# TTL640x480-DIODE.net
KiCad netlist of a schematic drawn in EAGLE
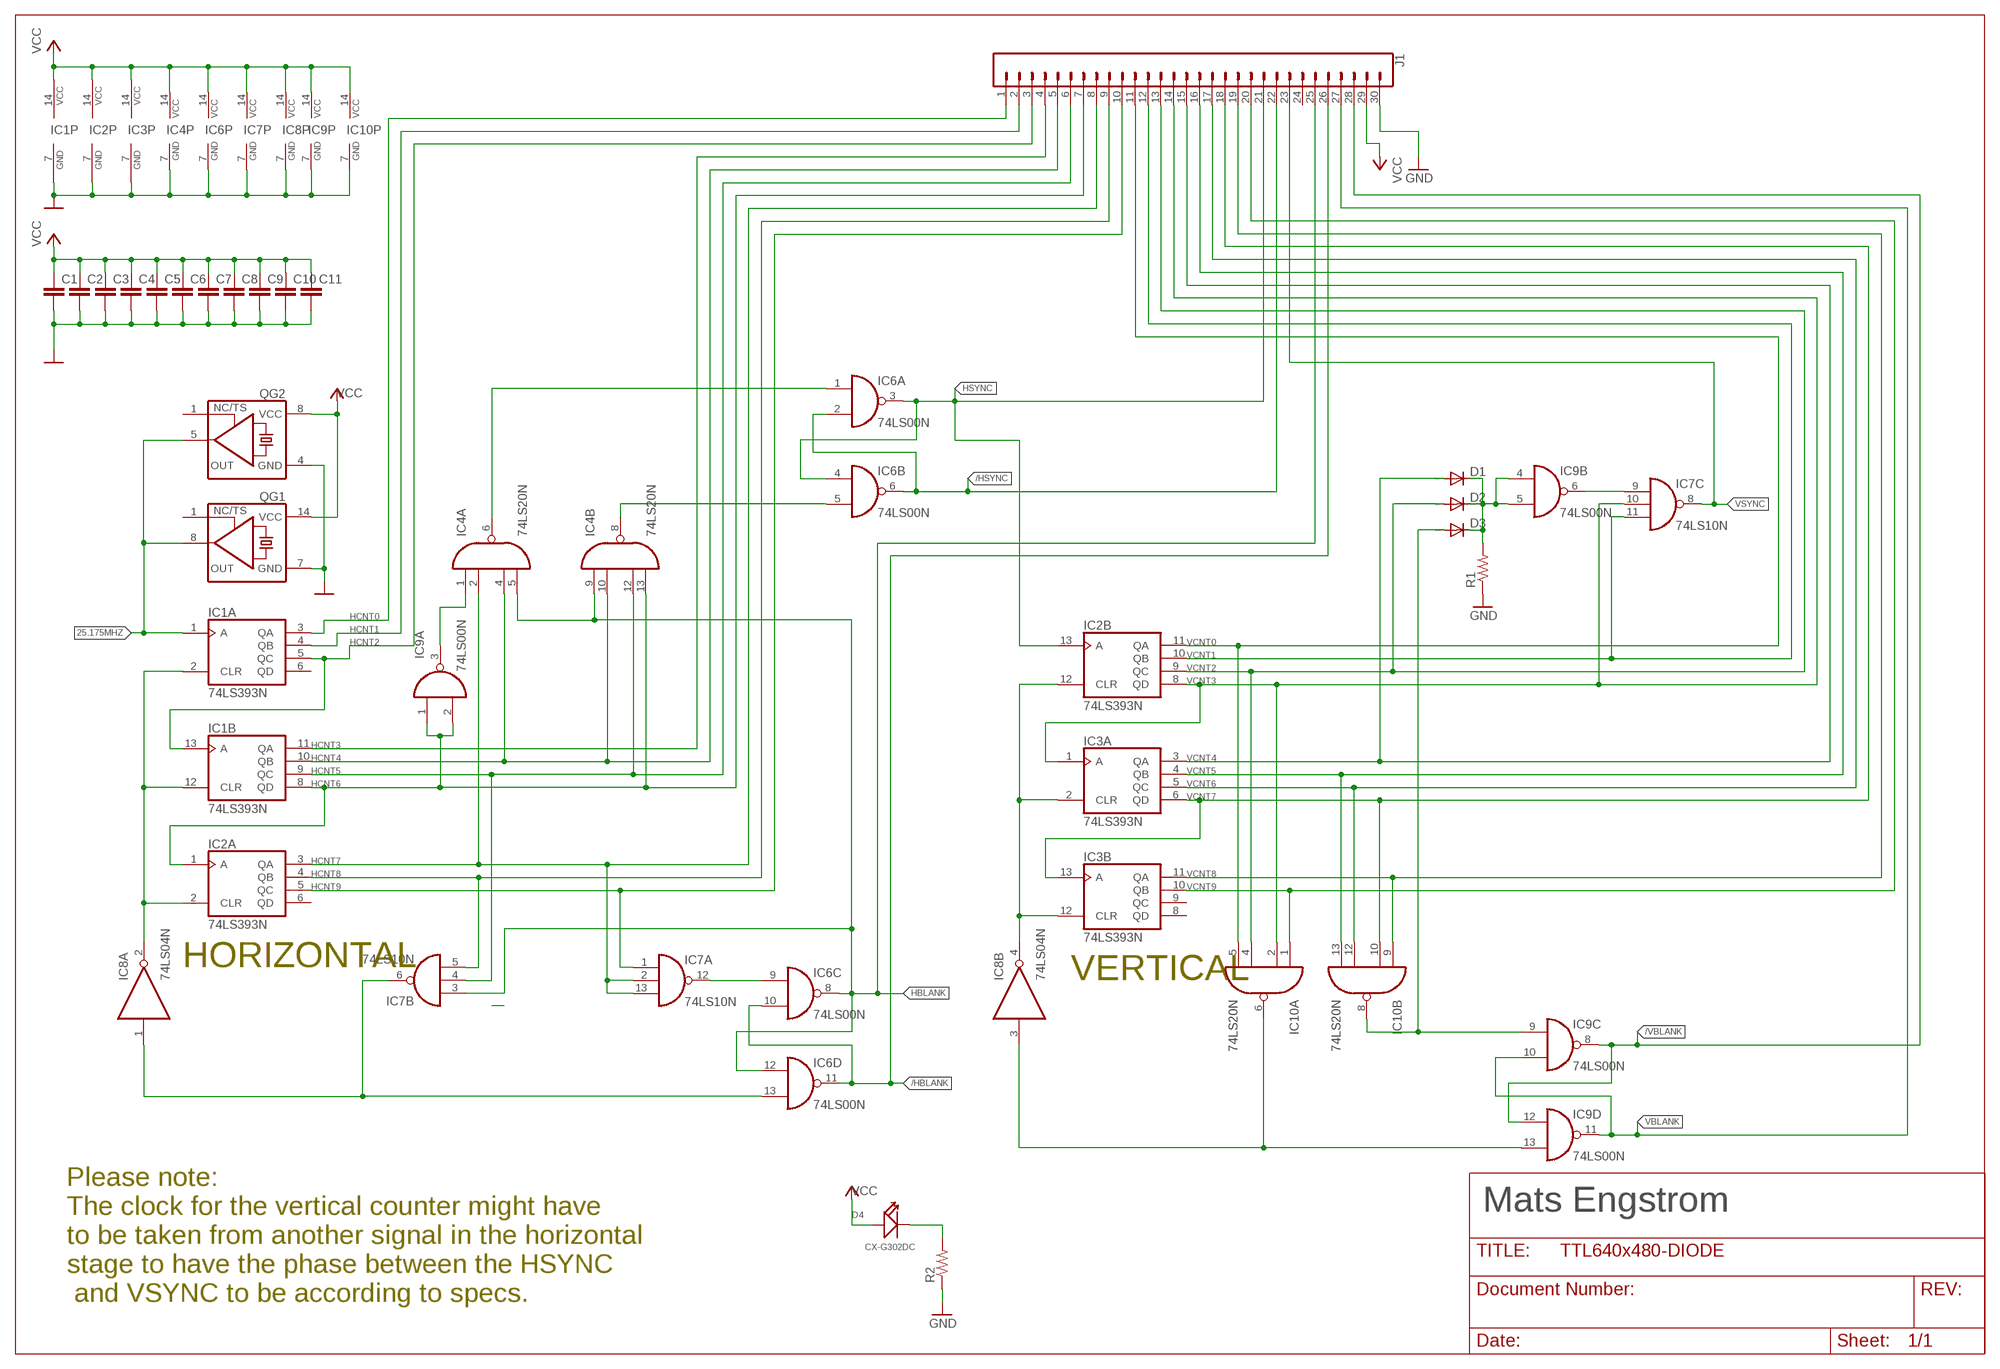
[diagram p0: schematic, sheet 1]

(export (version "E")
  (design (tool "Eeschema 10.0.6"))
  (components
    (comp (ref "C1")
      (value "C-EU050-024X044")
      (footprint "eagle-import:C050-024X044")
      (libsource (lib "eagle-import") (part "C-EU050-024X044"))
    )
    (comp (ref "C2")
      (value "C-EU050-024X044")
      (footprint "eagle-import:C050-024X044")
      (libsource (lib "eagle-import") (part "C-EU050-024X044"))
    )
    (comp (ref "C3")
      (value "C-EU050-024X044")
      (footprint "eagle-import:C050-024X044")
      (libsource (lib "eagle-import") (part "C-EU050-024X044"))
    )
    (comp (ref "C4")
      (value "C-EU050-024X044")
      (footprint "eagle-import:C050-024X044")
      (libsource (lib "eagle-import") (part "C-EU050-024X044"))
    )
    (comp (ref "C5")
      (value "C-EU050-024X044")
      (footprint "eagle-import:C050-024X044")
      (libsource (lib "eagle-import") (part "C-EU050-024X044"))
    )
    (comp (ref "C6")
      (value "C-EU050-024X044")
      (footprint "eagle-import:C050-024X044")
      (libsource (lib "eagle-import") (part "C-EU050-024X044"))
    )
    (comp (ref "C7")
      (value "C-EU050-024X044")
      (footprint "eagle-import:C050-024X044")
      (libsource (lib "eagle-import") (part "C-EU050-024X044"))
    )
    (comp (ref "C8")
      (value "C-EU050-024X044")
      (footprint "eagle-import:C050-024X044")
      (libsource (lib "eagle-import") (part "C-EU050-024X044"))
    )
    (comp (ref "C9")
      (value "C-EU050-024X044")
      (footprint "eagle-import:C050-024X044")
      (libsource (lib "eagle-import") (part "C-EU050-024X044"))
    )
    (comp (ref "C10")
      (value "C-EU050-024X044")
      (footprint "eagle-import:C050-024X044")
      (libsource (lib "eagle-import") (part "C-EU050-024X044"))
    )
    (comp (ref "C11")
      (value "C-EU050-024X044")
      (footprint "eagle-import:C050-024X044")
      (libsource (lib "eagle-import") (part "C-EU050-024X044"))
    )
    (comp (ref "D1")
      (value "1N4148DO35-10")
      (footprint "eagle-import:DO35-10")
      (libsource (lib "eagle-import") (part "1N4148DO35-10"))
    )
    (comp (ref "D2")
      (value "1N4148DO35-10")
      (footprint "eagle-import:DO35-10")
      (libsource (lib "eagle-import") (part "1N4148DO35-10"))
    )
    (comp (ref "D3")
      (value "1N4148DO35-10")
      (footprint "eagle-import:DO35-10")
      (libsource (lib "eagle-import") (part "1N4148DO35-10"))
    )
    (comp (ref "D4")
      (value "CX-G302DC")
      (footprint "eagle-import:LED2-2.54-D3.0MM")
      (libsource (lib "eagle-import") (part "DIP-LED-GREEN-GREEN(2P-D3MM)"))
    )
    (comp (ref "IC1")
      (value "74LS393N")
      (footprint "eagle-import:DIL14")
      (libsource (lib "eagle-import") (part "74393NLS"))
    )
    (comp (ref "IC2")
      (value "74LS393N")
      (footprint "eagle-import:DIL14")
      (libsource (lib "eagle-import") (part "74393NLS"))
    )
    (comp (ref "IC3")
      (value "74LS393N")
      (footprint "eagle-import:DIL14")
      (libsource (lib "eagle-import") (part "74393NLS"))
    )
    (comp (ref "IC4")
      (value "74LS20N")
      (footprint "eagle-import:DIL14")
      (libsource (lib "eagle-import") (part "7420NLS"))
    )
    (comp (ref "IC6")
      (value "74LS00N")
      (footprint "eagle-import:DIL14")
      (libsource (lib "eagle-import") (part "7400NLS"))
    )
    (comp (ref "IC7")
      (value "74LS10N")
      (footprint "eagle-import:DIL14")
      (libsource (lib "eagle-import") (part "7410NLS"))
    )
    (comp (ref "IC8")
      (value "74LS04N")
      (footprint "eagle-import:DIL14")
      (libsource (lib "eagle-import") (part "7404NLS"))
    )
    (comp (ref "IC9")
      (value "74LS00N")
      (footprint "eagle-import:DIL14")
      (libsource (lib "eagle-import") (part "7400NLS"))
    )
    (comp (ref "IC10")
      (value "74LS20N")
      (footprint "eagle-import:DIL14")
      (libsource (lib "eagle-import") (part "7420NLS"))
    )
    (comp (ref "J1")
      (value "CONN_30")
      (footprint "eagle-import:1X30")
      (libsource (lib "eagle-import") (part "CONN_30"))
    )
    (comp (ref "QG1")
      (value "XO-14")
      (footprint "eagle-import:DIL14S")
      (libsource (lib "eagle-import") (part "XO-14"))
    )
    (comp (ref "QG2")
      (value "XO-8")
      (footprint "eagle-import:DIL08S")
      (libsource (lib "eagle-import") (part "XO-8"))
    )
    (comp (ref "R1")
      (value "R-US_0204/7")
      (footprint "eagle-import:0204_7")
      (libsource (lib "eagle-import") (part "R-US_0204/7"))
    )
    (comp (ref "R2")
      (value "R-US_0204/7")
      (footprint "eagle-import:0204_7")
      (libsource (lib "eagle-import") (part "R-US_0204/7"))
    )
  )
  (nets
    (net (code "1") (name "/HCNT0") (class "Default")
      (node (ref "IC1") (pin "3") (pinfunction "QA_3") (pintype "output"))
      (node (ref "J1") (pin "1") (pinfunction "1_1") (pintype "passive"))
    )
    (net (code "2") (name "/HCNT1") (class "Default")
      (node (ref "IC1") (pin "4") (pinfunction "QB_4") (pintype "output"))
      (node (ref "J1") (pin "2") (pinfunction "2_2") (pintype "passive"))
    )
    (net (code "3") (name "/HCNT2") (class "Default")
      (node (ref "IC1") (pin "13") (pinfunction "A_13") (pintype "input"))
      (node (ref "IC1") (pin "5") (pinfunction "QC_5") (pintype "output"))
      (node (ref "J1") (pin "3") (pinfunction "3_3") (pintype "passive"))
    )
    (net (code "4") (name "/HCNT3") (class "Default")
      (node (ref "IC1") (pin "11") (pinfunction "QA_11") (pintype "output"))
      (node (ref "J1") (pin "4") (pinfunction "4_4") (pintype "passive"))
    )
    (net (code "5") (name "/HCNT4") (class "Default")
      (node (ref "IC1") (pin "10") (pinfunction "QB_10") (pintype "output"))
      (node (ref "IC4") (pin "10") (pinfunction "I1_10") (pintype "input"))
      (node (ref "IC4") (pin "4") (pinfunction "I2_4") (pintype "input"))
      (node (ref "J1") (pin "5") (pinfunction "5_5") (pintype "passive"))
    )
    (net (code "6") (name "/HCNT5") (class "Default")
      (node (ref "IC1") (pin "9") (pinfunction "QC_9") (pintype "output"))
      (node (ref "IC4") (pin "12") (pinfunction "I2_12") (pintype "input"))
      (node (ref "IC7") (pin "4") (pinfunction "I1_4") (pintype "input"))
      (node (ref "J1") (pin "6") (pinfunction "6_6") (pintype "passive"))
    )
    (net (code "7") (name "/HCNT6") (class "Default")
      (node (ref "IC1") (pin "8") (pinfunction "QD_8") (pintype "output"))
      (node (ref "IC2") (pin "1") (pinfunction "A_1") (pintype "input"))
      (node (ref "IC4") (pin "13") (pinfunction "I3_13") (pintype "input"))
      (node (ref "IC9") (pin "1") (pinfunction "I0_1") (pintype "input"))
      (node (ref "IC9") (pin "2") (pinfunction "I1_2") (pintype "input"))
      (node (ref "J1") (pin "7") (pinfunction "7_7") (pintype "passive"))
    )
    (net (code "8") (name "/HCNT7") (class "Default")
      (node (ref "IC2") (pin "3") (pinfunction "QA_3") (pintype "output"))
      (node (ref "IC4") (pin "2") (pinfunction "I1_2") (pintype "input"))
      (node (ref "IC7") (pin "13") (pinfunction "I2_13") (pintype "input"))
      (node (ref "IC7") (pin "2") (pinfunction "I1_2") (pintype "input"))
      (node (ref "J1") (pin "8") (pinfunction "8_8") (pintype "passive"))
    )
    (net (code "9") (name "/HCNT8") (class "Default")
      (node (ref "IC2") (pin "4") (pinfunction "QB_4") (pintype "output"))
      (node (ref "IC7") (pin "5") (pinfunction "I2_5") (pintype "input"))
      (node (ref "J1") (pin "9") (pinfunction "9_9") (pintype "passive"))
    )
    (net (code "10") (name "/HCNT9") (class "Default")
      (node (ref "IC2") (pin "5") (pinfunction "QC_5") (pintype "output"))
      (node (ref "IC7") (pin "1") (pinfunction "I0_1") (pintype "input"))
      (node (ref "J1") (pin "10") (pinfunction "10_10") (pintype "passive"))
    )
    (net (code "11") (name "/VCNT0") (class "Default")
      (node (ref "IC10") (pin "5") (pinfunction "I3_5") (pintype "input"))
      (node (ref "IC2") (pin "11") (pinfunction "QA_11") (pintype "output"))
      (node (ref "J1") (pin "11") (pinfunction "11_11") (pintype "passive"))
    )
    (net (code "12") (name "/VCNT1") (class "Default")
      (node (ref "IC2") (pin "10") (pinfunction "QB_10") (pintype "output"))
      (node (ref "IC7") (pin "11") (pinfunction "I2_11") (pintype "input"))
      (node (ref "J1") (pin "12") (pinfunction "12_12") (pintype "passive"))
    )
    (net (code "13") (name "/VCNT2") (class "Default")
      (node (ref "D2") (pin "A") (pinfunction "A_A") (pintype "passive"))
      (node (ref "IC10") (pin "4") (pinfunction "I2_4") (pintype "input"))
      (node (ref "IC2") (pin "9") (pinfunction "QC_9") (pintype "output"))
      (node (ref "J1") (pin "13") (pinfunction "13_13") (pintype "passive"))
    )
    (net (code "14") (name "/VCNT3") (class "Default")
      (node (ref "IC10") (pin "2") (pinfunction "I1_2") (pintype "input"))
      (node (ref "IC2") (pin "8") (pinfunction "QD_8") (pintype "output"))
      (node (ref "IC3") (pin "1") (pinfunction "A_1") (pintype "input"))
      (node (ref "IC7") (pin "10") (pinfunction "I1_10") (pintype "input"))
      (node (ref "J1") (pin "14") (pinfunction "14_14") (pintype "passive"))
    )
    (net (code "15") (name "/VCNT4") (class "Default")
      (node (ref "D1") (pin "A") (pinfunction "A_A") (pintype "passive"))
      (node (ref "IC3") (pin "3") (pinfunction "QA_3") (pintype "output"))
      (node (ref "J1") (pin "15") (pinfunction "15_15") (pintype "passive"))
    )
    (net (code "16") (name "/VCNT5") (class "Default")
      (node (ref "IC10") (pin "13") (pinfunction "I3_13") (pintype "input"))
      (node (ref "IC3") (pin "4") (pinfunction "QB_4") (pintype "output"))
      (node (ref "J1") (pin "16") (pinfunction "16_16") (pintype "passive"))
    )
    (net (code "17") (name "/VCNT6") (class "Default")
      (node (ref "IC10") (pin "12") (pinfunction "I2_12") (pintype "input"))
      (node (ref "IC3") (pin "5") (pinfunction "QC_5") (pintype "output"))
      (node (ref "J1") (pin "17") (pinfunction "17_17") (pintype "passive"))
    )
    (net (code "18") (name "/VCNT7") (class "Default")
      (node (ref "IC10") (pin "10") (pinfunction "I1_10") (pintype "input"))
      (node (ref "IC3") (pin "13") (pinfunction "A_13") (pintype "input"))
      (node (ref "IC3") (pin "6") (pinfunction "QD_6") (pintype "output"))
      (node (ref "J1") (pin "18") (pinfunction "18_18") (pintype "passive"))
    )
    (net (code "19") (name "/VCNT8") (class "Default")
      (node (ref "IC10") (pin "9") (pinfunction "I0_9") (pintype "input"))
      (node (ref "IC3") (pin "11") (pinfunction "QA_11") (pintype "output"))
      (node (ref "J1") (pin "19") (pinfunction "19_19") (pintype "passive"))
    )
    (net (code "20") (name "/VCNT9") (class "Default")
      (node (ref "IC10") (pin "1") (pinfunction "I0_1") (pintype "input"))
      (node (ref "IC3") (pin "10") (pinfunction "QB_10") (pintype "output"))
      (node (ref "J1") (pin "20") (pinfunction "20_20") (pintype "passive"))
    )
    (net (code "21") (name "25.175MHZ") (class "Default")
      (node (ref "IC1") (pin "1") (pinfunction "A_1") (pintype "input"))
      (node (ref "QG1") (pin "8") (pinfunction "OUT_8") (pintype "output"))
      (node (ref "QG2") (pin "5") (pinfunction "OUT_5") (pintype "output"))
    )
    (net (code "22") (name "GND") (class "Default")
      (node (ref "C1") (pin "2") (pinfunction "2_2") (pintype "passive"))
      (node (ref "C10") (pin "2") (pinfunction "2_2") (pintype "passive"))
      (node (ref "C11") (pin "2") (pinfunction "2_2") (pintype "passive"))
      (node (ref "C2") (pin "2") (pinfunction "2_2") (pintype "passive"))
      (node (ref "C3") (pin "2") (pinfunction "2_2") (pintype "passive"))
      (node (ref "C4") (pin "2") (pinfunction "2_2") (pintype "passive"))
      (node (ref "C5") (pin "2") (pinfunction "2_2") (pintype "passive"))
      (node (ref "C6") (pin "2") (pinfunction "2_2") (pintype "passive"))
      (node (ref "C7") (pin "2") (pinfunction "2_2") (pintype "passive"))
      (node (ref "C8") (pin "2") (pinfunction "2_2") (pintype "passive"))
      (node (ref "C9") (pin "2") (pinfunction "2_2") (pintype "passive"))
      (node (ref "IC1") (pin "7") (pinfunction "GND_7") (pintype "power_in"))
      (node (ref "IC10") (pin "7") (pinfunction "GND_7") (pintype "power_in"))
      (node (ref "IC2") (pin "7") (pinfunction "GND_7") (pintype "power_in"))
      (node (ref "IC3") (pin "7") (pinfunction "GND_7") (pintype "power_in"))
      (node (ref "IC4") (pin "7") (pinfunction "GND_7") (pintype "power_in"))
      (node (ref "IC6") (pin "7") (pinfunction "GND_7") (pintype "power_in"))
      (node (ref "IC7") (pin "7") (pinfunction "GND_7") (pintype "power_in"))
      (node (ref "IC8") (pin "7") (pinfunction "GND_7") (pintype "power_in"))
      (node (ref "IC9") (pin "7") (pinfunction "GND_7") (pintype "power_in"))
      (node (ref "J1") (pin "30") (pinfunction "30_30") (pintype "passive"))
      (node (ref "QG1") (pin "7") (pinfunction "GND_7") (pintype "power_in"))
      (node (ref "QG2") (pin "4") (pinfunction "GND_4") (pintype "power_in"))
      (node (ref "R1") (pin "1") (pinfunction "1_1") (pintype "passive"))
      (node (ref "R2") (pin "1") (pinfunction "1_1") (pintype "passive"))
    )
    (net (code "23") (name "HBLANK") (class "Default")
      (node (ref "IC4") (pin "5") (pinfunction "I3_5") (pintype "input"))
      (node (ref "IC4") (pin "9") (pinfunction "I0_9") (pintype "input"))
      (node (ref "IC6") (pin "12") (pinfunction "I0_12") (pintype "input"))
      (node (ref "IC6") (pin "8") (pinfunction "O_8") (pintype "output"))
      (node (ref "IC7") (pin "3") (pinfunction "I0_3") (pintype "input"))
      (node (ref "J1") (pin "25") (pinfunction "25_25") (pintype "passive"))
    )
    (net (code "24") (name "HSYNC") (class "Default")
      (node (ref "IC2") (pin "13") (pinfunction "A_13") (pintype "input"))
      (node (ref "IC6") (pin "3") (pinfunction "O_3") (pintype "output"))
      (node (ref "IC6") (pin "4") (pinfunction "I0_4") (pintype "input"))
      (node (ref "J1") (pin "21") (pinfunction "21_21") (pintype "passive"))
    )
    (net (code "25") (name "Net-(D4--)") (class "Default")
      (node (ref "D4") (pin "K") (pinfunction "-_K") (pintype "passive"))
      (node (ref "R2") (pin "2") (pinfunction "2_2") (pintype "passive"))
    )
    (net (code "26") (name "Net-(IC1A-CLR)") (class "Default")
      (node (ref "IC1") (pin "12") (pinfunction "CLR_12") (pintype "input"))
      (node (ref "IC1") (pin "2") (pinfunction "CLR_2") (pintype "input"))
      (node (ref "IC2") (pin "2") (pinfunction "CLR_2") (pintype "input"))
      (node (ref "IC8") (pin "2") (pinfunction "O_2") (pintype "output"))
    )
    (net (code "27") (name "Net-(IC2B-CLR)") (class "Default")
      (node (ref "IC2") (pin "12") (pinfunction "CLR_12") (pintype "input"))
      (node (ref "IC3") (pin "12") (pinfunction "CLR_12") (pintype "input"))
      (node (ref "IC3") (pin "2") (pinfunction "CLR_2") (pintype "input"))
      (node (ref "IC8") (pin "4") (pinfunction "O_4") (pintype "output"))
    )
    (net (code "28") (name "Net-(IC4A-I0)") (class "Default")
      (node (ref "IC4") (pin "1") (pinfunction "I0_1") (pintype "input"))
      (node (ref "IC9") (pin "3") (pinfunction "O_3") (pintype "output"))
    )
    (net (code "29") (name "Net-(IC4A-O)") (class "Default")
      (node (ref "IC4") (pin "6") (pinfunction "O_6") (pintype "output"))
      (node (ref "IC6") (pin "1") (pinfunction "I0_1") (pintype "input"))
    )
    (net (code "30") (name "Net-(IC4B-O)") (class "Default")
      (node (ref "IC4") (pin "8") (pinfunction "O_8") (pintype "output"))
      (node (ref "IC6") (pin "5") (pinfunction "I1_5") (pintype "input"))
    )
    (net (code "31") (name "Net-(IC6C-I0)") (class "Default")
      (node (ref "IC6") (pin "9") (pinfunction "I0_9") (pintype "input"))
      (node (ref "IC7") (pin "12") (pinfunction "O_12") (pintype "output"))
    )
    (net (code "32") (name "Net-(IC6D-I1)") (class "Default")
      (node (ref "IC6") (pin "13") (pinfunction "I1_13") (pintype "input"))
      (node (ref "IC7") (pin "6") (pinfunction "O_6") (pintype "output"))
      (node (ref "IC8") (pin "1") (pinfunction "I_1") (pintype "input"))
    )
    (net (code "33") (name "Net-(IC7C-I0)") (class "Default")
      (node (ref "IC7") (pin "9") (pinfunction "I0_9") (pintype "input"))
      (node (ref "IC9") (pin "6") (pinfunction "O_6") (pintype "output"))
    )
    (net (code "34") (name "Net-(IC9B-I0)") (class "Default")
      (node (ref "D1") (pin "C") (pinfunction "C_C") (pintype "passive"))
      (node (ref "D2") (pin "C") (pinfunction "C_C") (pintype "passive"))
      (node (ref "D3") (pin "C") (pinfunction "C_C") (pintype "passive"))
      (node (ref "IC9") (pin "4") (pinfunction "I0_4") (pintype "input"))
      (node (ref "IC9") (pin "5") (pinfunction "I1_5") (pintype "input"))
      (node (ref "R1") (pin "2") (pinfunction "2_2") (pintype "passive"))
    )
    (net (code "35") (name "Net-(IC10A-O)") (class "Default")
      (node (ref "IC10") (pin "6") (pinfunction "O_6") (pintype "output"))
      (node (ref "IC8") (pin "3") (pinfunction "I_3") (pintype "input"))
      (node (ref "IC9") (pin "13") (pinfunction "I1_13") (pintype "input"))
    )
    (net (code "36") (name "Net-(IC10B-O)") (class "Default")
      (node (ref "D3") (pin "A") (pinfunction "A_A") (pintype "passive"))
      (node (ref "IC10") (pin "8") (pinfunction "O_8") (pintype "output"))
      (node (ref "IC9") (pin "9") (pinfunction "I0_9") (pintype "input"))
    )
    (net (code "37") (name "VBLANK") (class "Default")
      (node (ref "IC9") (pin "10") (pinfunction "I1_10") (pintype "input"))
      (node (ref "IC9") (pin "11") (pinfunction "O_11") (pintype "output"))
      (node (ref "J1") (pin "27") (pinfunction "27_27") (pintype "passive"))
    )
    (net (code "38") (name "VCC") (class "Default")
      (node (ref "C1") (pin "1") (pinfunction "1_1") (pintype "passive"))
      (node (ref "C10") (pin "1") (pinfunction "1_1") (pintype "passive"))
      (node (ref "C11") (pin "1") (pinfunction "1_1") (pintype "passive"))
      (node (ref "C2") (pin "1") (pinfunction "1_1") (pintype "passive"))
      (node (ref "C3") (pin "1") (pinfunction "1_1") (pintype "passive"))
      (node (ref "C4") (pin "1") (pinfunction "1_1") (pintype "passive"))
      (node (ref "C5") (pin "1") (pinfunction "1_1") (pintype "passive"))
      (node (ref "C6") (pin "1") (pinfunction "1_1") (pintype "passive"))
      (node (ref "C7") (pin "1") (pinfunction "1_1") (pintype "passive"))
      (node (ref "C8") (pin "1") (pinfunction "1_1") (pintype "passive"))
      (node (ref "C9") (pin "1") (pinfunction "1_1") (pintype "passive"))
      (node (ref "D4") (pin "A") (pinfunction "+_A") (pintype "passive"))
      (node (ref "IC1") (pin "14") (pinfunction "VCC_14") (pintype "power_in"))
      (node (ref "IC10") (pin "14") (pinfunction "VCC_14") (pintype "power_in"))
      (node (ref "IC2") (pin "14") (pinfunction "VCC_14") (pintype "power_in"))
      (node (ref "IC3") (pin "14") (pinfunction "VCC_14") (pintype "power_in"))
      (node (ref "IC4") (pin "14") (pinfunction "VCC_14") (pintype "power_in"))
      (node (ref "IC6") (pin "14") (pinfunction "VCC_14") (pintype "power_in"))
      (node (ref "IC7") (pin "14") (pinfunction "VCC_14") (pintype "power_in"))
      (node (ref "IC8") (pin "14") (pinfunction "VCC_14") (pintype "power_in"))
      (node (ref "IC9") (pin "14") (pinfunction "VCC_14") (pintype "power_in"))
      (node (ref "J1") (pin "29") (pinfunction "29_29") (pintype "passive"))
      (node (ref "QG1") (pin "14") (pinfunction "VCC_14") (pintype "power_in"))
      (node (ref "QG2") (pin "8") (pinfunction "VCC_8") (pintype "power_in"))
    )
    (net (code "39") (name "VSYNC") (class "Default")
      (node (ref "IC7") (pin "8") (pinfunction "O_8") (pintype "output"))
      (node (ref "J1") (pin "23") (pinfunction "23_23") (pintype "passive"))
    )
    (net (code "40") (name "unconnected-(IC1A-QD-Pad6)") (class "Default")
      (node (ref "IC1") (pin "6") (pinfunction "QD_6") (pintype "output"))
    )
    (net (code "41") (name "unconnected-(IC2A-QD-Pad6)") (class "Default")
      (node (ref "IC2") (pin "6") (pinfunction "QD_6") (pintype "output"))
    )
    (net (code "42") (name "unconnected-(IC3B-QC-Pad9)") (class "Default")
      (node (ref "IC3") (pin "9") (pinfunction "QC_9") (pintype "output"))
    )
    (net (code "43") (name "unconnected-(IC3B-QD-Pad8)") (class "Default")
      (node (ref "IC3") (pin "8") (pinfunction "QD_8") (pintype "output"))
    )
    (net (code "44") (name "unconnected-(J1-Pad24)") (class "Default")
      (node (ref "J1") (pin "24") (pinfunction "24_24") (pintype "passive"))
    )
    (net (code "45") (name "unconnected-(QG1-TS-Pad1)") (class "Default")
      (node (ref "QG1") (pin "1") (pinfunction "TS_1") (pintype "passive"))
    )
    (net (code "46") (name "unconnected-(QG2-TS-Pad1)") (class "Default")
      (node (ref "QG2") (pin "1") (pinfunction "TS_1") (pintype "passive"))
    )
    (net (code "47") (name "{slash}HBLANK") (class "Default")
      (node (ref "IC6") (pin "10") (pinfunction "I1_10") (pintype "input"))
      (node (ref "IC6") (pin "11") (pinfunction "O_11") (pintype "output"))
      (node (ref "J1") (pin "26") (pinfunction "26_26") (pintype "passive"))
    )
    (net (code "48") (name "{slash}HSYNC") (class "Default")
      (node (ref "IC6") (pin "2") (pinfunction "I1_2") (pintype "input"))
      (node (ref "IC6") (pin "6") (pinfunction "O_6") (pintype "output"))
      (node (ref "J1") (pin "22") (pinfunction "22_22") (pintype "passive"))
    )
    (net (code "49") (name "{slash}VBLANK") (class "Default")
      (node (ref "IC9") (pin "12") (pinfunction "I0_12") (pintype "input"))
      (node (ref "IC9") (pin "8") (pinfunction "O_8") (pintype "output"))
      (node (ref "J1") (pin "28") (pinfunction "28_28") (pintype "passive"))
    )
  )
)
